# sram_rom.net
KiCad netlist of a schematic drawn in Altium Designer
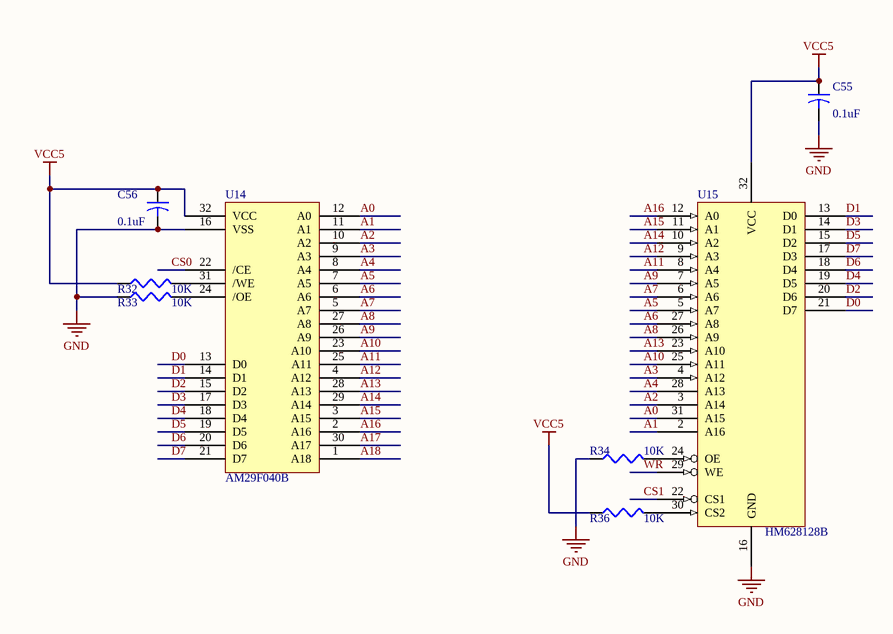
[diagram p0: sram_rom.SchDoc]

(export (version "E")
  (design (tool "Eeschema 10.0.6"))
  (components
    (comp (ref "C55")
      (value "0.1uF")
      (footprint "CAPC1608L")
      (description "Capacitor")
      (fields (field (name "Comment") "Cap2") (field (name "PUBLISHER") "Altium Limited"))
      (libsource (lib "Miscellaneous Devices") (part "Cap2"))
    )
    (comp (ref "C56")
      (value "0.1uF")
      (footprint "CAPC1608L")
      (description "Capacitor")
      (fields (field (name "Comment") "Cap2") (field (name "PUBLISHER") "Altium Limited"))
      (libsource (lib "Miscellaneous Devices") (part "Cap2"))
    )
    (comp (ref "R32")
      (value "10K")
      (footprint "RESC1608N")
      (description "Resistor")
      (fields (field (name "Comment") "Res3") (field (name "PUBLISHER") "Altium Limited"))
      (libsource (lib "Miscellaneous Devices") (part "Res3"))
    )
    (comp (ref "R33")
      (value "10K")
      (footprint "RESC1608N")
      (description "Resistor")
      (fields (field (name "Comment") "Res3") (field (name "PUBLISHER") "Altium Limited"))
      (libsource (lib "Miscellaneous Devices") (part "Res3"))
    )
    (comp (ref "R34")
      (value "10K")
      (footprint "RESC1608N")
      (description "Resistor")
      (fields (field (name "Comment") "Res3") (field (name "PUBLISHER") "Altium Limited"))
      (libsource (lib "Miscellaneous Devices") (part "Res3"))
    )
    (comp (ref "R36")
      (value "10K")
      (footprint "RESC1608N")
      (description "Resistor")
      (fields (field (name "Comment") "Res3") (field (name "PUBLISHER") "Altium Limited"))
      (libsource (lib "Miscellaneous Devices") (part "Res3"))
    )
    (comp (ref "U14")
      (value "AM29F040B")
      (footprint "PLCCS32")
      (description "512KBit x 8 ROM")
      (libsource (lib "ee52_tago_sch") (part "AM29F040B"))
    )
    (comp (ref "U15")
      (value "HM628128B")
      (footprint "DIP32")
      (description "1 M SRAM (128-kword x 8-bit)")
      (libsource (lib "eecs5x") (part "HM628128B"))
    )
  )
  (nets
    (net (code "1") (name "/A0") (class "Default")
      (node (ref "U14") (pin "12") (pinfunction "A0_12") (pintype "passive"))
      (node (ref "U15") (pin "31") (pinfunction "A15_31") (pintype "passive"))
    )
    (net (code "2") (name "/A1") (class "Default")
      (node (ref "U14") (pin "11") (pinfunction "A1_11") (pintype "passive"))
      (node (ref "U15") (pin "2") (pinfunction "A16_2") (pintype "passive"))
    )
    (net (code "3") (name "/A2") (class "Default")
      (node (ref "U14") (pin "10") (pinfunction "A2_10") (pintype "passive"))
      (node (ref "U15") (pin "3") (pinfunction "A14_3") (pintype "passive"))
    )
    (net (code "4") (name "/A3") (class "Default")
      (node (ref "U14") (pin "9") (pinfunction "A3_9") (pintype "passive"))
      (node (ref "U15") (pin "4") (pinfunction "A12_4") (pintype "input"))
    )
    (net (code "5") (name "/A4") (class "Default")
      (node (ref "U14") (pin "8") (pinfunction "A4_8") (pintype "passive"))
      (node (ref "U15") (pin "28") (pinfunction "A13_28") (pintype "passive"))
    )
    (net (code "6") (name "/A5") (class "Default")
      (node (ref "U14") (pin "7") (pinfunction "A5_7") (pintype "passive"))
      (node (ref "U15") (pin "5") (pinfunction "A7_5") (pintype "input"))
    )
    (net (code "7") (name "/A6") (class "Default")
      (node (ref "U14") (pin "6") (pinfunction "A6_6") (pintype "passive"))
      (node (ref "U15") (pin "27") (pinfunction "A8_27") (pintype "input"))
    )
    (net (code "8") (name "/A7") (class "Default")
      (node (ref "U14") (pin "5") (pinfunction "A7_5") (pintype "passive"))
      (node (ref "U15") (pin "6") (pinfunction "A6_6") (pintype "input"))
    )
    (net (code "9") (name "/A8") (class "Default")
      (node (ref "U14") (pin "27") (pinfunction "A8_27") (pintype "passive"))
      (node (ref "U15") (pin "26") (pinfunction "A9_26") (pintype "input"))
    )
    (net (code "10") (name "/A9") (class "Default")
      (node (ref "U14") (pin "26") (pinfunction "A9_26") (pintype "passive"))
      (node (ref "U15") (pin "7") (pinfunction "A5_7") (pintype "input"))
    )
    (net (code "11") (name "/A10") (class "Default")
      (node (ref "U14") (pin "23") (pinfunction "A10_23") (pintype "passive"))
      (node (ref "U15") (pin "25") (pinfunction "A11_25") (pintype "input"))
    )
    (net (code "12") (name "/A11") (class "Default")
      (node (ref "U14") (pin "25") (pinfunction "A11_25") (pintype "passive"))
      (node (ref "U15") (pin "8") (pinfunction "A4_8") (pintype "input"))
    )
    (net (code "13") (name "/A12") (class "Default")
      (node (ref "U14") (pin "4") (pinfunction "A12_4") (pintype "passive"))
      (node (ref "U15") (pin "9") (pinfunction "A3_9") (pintype "input"))
    )
    (net (code "14") (name "/A13") (class "Default")
      (node (ref "U14") (pin "28") (pinfunction "A13_28") (pintype "passive"))
      (node (ref "U15") (pin "23") (pinfunction "A10_23") (pintype "input"))
    )
    (net (code "15") (name "/A14") (class "Default")
      (node (ref "U14") (pin "29") (pinfunction "A14_29") (pintype "passive"))
      (node (ref "U15") (pin "10") (pinfunction "A2_10") (pintype "input"))
    )
    (net (code "16") (name "/A15") (class "Default")
      (node (ref "U14") (pin "3") (pinfunction "A15_3") (pintype "passive"))
      (node (ref "U15") (pin "11") (pinfunction "A1_11") (pintype "input"))
    )
    (net (code "17") (name "/A16") (class "Default")
      (node (ref "U14") (pin "2") (pinfunction "A16_2") (pintype "passive"))
      (node (ref "U15") (pin "12") (pinfunction "A0_12") (pintype "input"))
    )
    (net (code "18") (name "/A17") (class "Default")
      (node (ref "U14") (pin "30") (pinfunction "A17_30") (pintype "passive"))
    )
    (net (code "19") (name "/A18") (class "Default")
      (node (ref "U14") (pin "1") (pinfunction "A18_1") (pintype "passive"))
    )
    (net (code "20") (name "/CS0") (class "Default")
      (node (ref "U14") (pin "22") (pinfunction "/CE_22") (pintype "passive"))
    )
    (net (code "21") (name "/CS1") (class "Default")
      (node (ref "U15") (pin "22") (pinfunction "CS1_22") (pintype "input"))
    )
    (net (code "22") (name "/D0") (class "Default")
      (node (ref "U14") (pin "13") (pinfunction "D0_13") (pintype "passive"))
      (node (ref "U15") (pin "21") (pinfunction "D7_21") (pintype "tri_state"))
    )
    (net (code "23") (name "/D1") (class "Default")
      (node (ref "U14") (pin "14") (pinfunction "D1_14") (pintype "passive"))
      (node (ref "U15") (pin "13") (pinfunction "D0_13") (pintype "tri_state"))
    )
    (net (code "24") (name "/D2") (class "Default")
      (node (ref "U14") (pin "15") (pinfunction "D2_15") (pintype "passive"))
      (node (ref "U15") (pin "20") (pinfunction "D6_20") (pintype "tri_state"))
    )
    (net (code "25") (name "/D3") (class "Default")
      (node (ref "U14") (pin "17") (pinfunction "D3_17") (pintype "passive"))
      (node (ref "U15") (pin "14") (pinfunction "D1_14") (pintype "tri_state"))
    )
    (net (code "26") (name "/D4") (class "Default")
      (node (ref "U14") (pin "18") (pinfunction "D4_18") (pintype "passive"))
      (node (ref "U15") (pin "19") (pinfunction "D5_19") (pintype "tri_state"))
    )
    (net (code "27") (name "/D5") (class "Default")
      (node (ref "U14") (pin "19") (pinfunction "D5_19") (pintype "passive"))
      (node (ref "U15") (pin "15") (pinfunction "D2_15") (pintype "tri_state"))
    )
    (net (code "28") (name "/D6") (class "Default")
      (node (ref "U14") (pin "20") (pinfunction "D6_20") (pintype "passive"))
      (node (ref "U15") (pin "18") (pinfunction "D4_18") (pintype "tri_state"))
    )
    (net (code "29") (name "/D7") (class "Default")
      (node (ref "U14") (pin "21") (pinfunction "D7_21") (pintype "passive"))
      (node (ref "U15") (pin "17") (pinfunction "D3_17") (pintype "tri_state"))
    )
    (net (code "30") (name "/WR") (class "Default")
      (node (ref "U15") (pin "29") (pinfunction "WE_29") (pintype "input"))
    )
    (net (code "31") (name "GND") (class "Default")
      (node (ref "C55") (pin "2") (pinfunction "2_2") (pintype "passive"))
      (node (ref "C56") (pin "2") (pinfunction "2_2") (pintype "passive"))
      (node (ref "R33") (pin "1") (pinfunction "1_1") (pintype "passive"))
      (node (ref "R34") (pin "1") (pinfunction "1_1") (pintype "passive"))
      (node (ref "U14") (pin "16") (pinfunction "VSS_16") (pintype "passive"))
      (node (ref "U15") (pin "16") (pinfunction "GND_16") (pintype "power_in"))
    )
    (net (code "32") (name "Net-(U14-{slash}OE)") (class "Default")
      (node (ref "R33") (pin "2") (pinfunction "2_2") (pintype "passive"))
      (node (ref "U14") (pin "24") (pinfunction "/OE_24") (pintype "passive"))
    )
    (net (code "33") (name "Net-(U14-{slash}WE)") (class "Default")
      (node (ref "R32") (pin "2") (pinfunction "2_2") (pintype "passive"))
      (node (ref "U14") (pin "31") (pinfunction "/WE_31") (pintype "passive"))
    )
    (net (code "34") (name "Net-(U15-CS2)") (class "Default")
      (node (ref "R36") (pin "2") (pinfunction "2_2") (pintype "passive"))
      (node (ref "U15") (pin "30") (pinfunction "CS2_30") (pintype "input"))
    )
    (net (code "35") (name "Net-(U15-OE)") (class "Default")
      (node (ref "R34") (pin "2") (pinfunction "2_2") (pintype "passive"))
      (node (ref "U15") (pin "24") (pinfunction "OE_24") (pintype "input"))
    )
    (net (code "36") (name "VCC5") (class "Default")
      (node (ref "C55") (pin "1") (pinfunction "1_1") (pintype "passive"))
      (node (ref "C56") (pin "1") (pinfunction "1_1") (pintype "passive"))
      (node (ref "R32") (pin "1") (pinfunction "1_1") (pintype "passive"))
      (node (ref "R36") (pin "1") (pinfunction "1_1") (pintype "passive"))
      (node (ref "U14") (pin "32") (pinfunction "VCC_32") (pintype "passive"))
      (node (ref "U15") (pin "32") (pinfunction "VCC_32") (pintype "power_in"))
    )
  )
)
